# EthernetPhy.net
KiCad netlist of a schematic drawn in Altium Designer
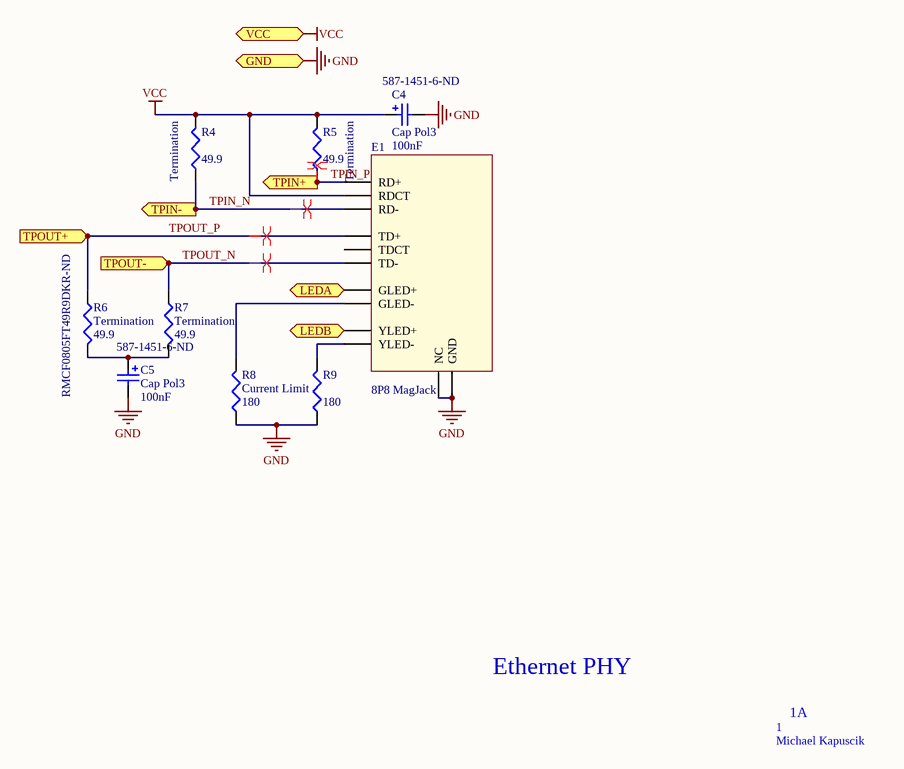
[diagram p0: EthernetPhy.SchDoc]

(export (version "E")
  (design (tool "Eeschema 10.0.6"))
  (components
    (comp (ref "C4")
      (value "Cap Pol3")
      (footprint "C0805")
      (description "Polarized Capacitor (Surface Mount)")
      (fields
        (field (name "ALTIUM_VALUE") "100nF")
        (field (name "SUPPLIER PART NUMBER 1") "587-1451-6-ND")
        (field (name "MANUFACTURER") "Taiyo Yuden")
        (field (name "MANUFACTURER PART NUMBER") "EMK105B7104KV-F")
        (field (name "PUBLISHER") "Altium Limited")
      )
      (libsource (lib "Miscellaneous Devices") (part "Cap Pol3"))
    )
    (comp (ref "C5")
      (value "Cap Pol3")
      (footprint "C0805")
      (description "Polarized Capacitor (Surface Mount)")
      (fields
        (field (name "ALTIUM_VALUE") "100nF")
        (field (name "SUPPLIER PART NUMBER 1") "587-1451-6-ND")
        (field (name "MANUFACTURER") "Taiyo Yuden")
        (field (name "MANUFACTURER PART NUMBER") "EMK105B7104KV-F")
        (field (name "PUBLISHER") "Altium Limited")
      )
      (libsource (lib "Miscellaneous Devices") (part "Cap Pol3"))
    )
    (comp (ref "E1")
      (value "8P8 MagJack")
      (footprint "HR911105")
      (libsource (lib "Miscellaneous Devices") (part "8P8 MagJack"))
    )
    (comp (ref "R4")
      (value "Termination")
      (footprint "J1-0603")
      (description "Resistor")
      (fields (field (name "ALTIUM_VALUE") "49.9") (field (name "PUBLISHER") "Altium Limited"))
      (libsource (lib "Miscellaneous Devices") (part "Res3"))
    )
    (comp (ref "R5")
      (value "Termination")
      (footprint "J1-0603")
      (description "Resistor")
      (fields (field (name "ALTIUM_VALUE") "49.9") (field (name "PUBLISHER") "Altium Limited"))
      (libsource (lib "Miscellaneous Devices") (part "Res3"))
    )
    (comp (ref "R6")
      (value "Termination")
      (footprint "J1-0603")
      (description "Resistor")
      (fields
        (field (name "ALTIUM_VALUE") "49.9")
        (field (name "SUPPLIER PART NUMBER 1") "RMCF0805FT49R9DKR-ND")
        (field (name "PUBLISHER") "Altium Limited")
      )
      (libsource (lib "Miscellaneous Devices") (part "Res3"))
    )
    (comp (ref "R7")
      (value "Termination")
      (footprint "J1-0603")
      (description "Resistor")
      (fields (field (name "ALTIUM_VALUE") "49.9") (field (name "PUBLISHER") "Altium Limited"))
      (libsource (lib "Miscellaneous Devices") (part "Res3"))
    )
    (comp (ref "R8")
      (value "Current Limit")
      (footprint "J1-0603")
      (description "Resistor")
      (fields (field (name "ALTIUM_VALUE") "180") (field (name "PUBLISHER") "Altium Limited"))
      (libsource (lib "Miscellaneous Devices") (part "Res3"))
    )
    (comp (ref "R9")
      (value "180")
      (footprint "J1-0603")
      (description "Resistor")
      (fields (field (name "Comment") "Current Limit") (field (name "PUBLISHER") "Altium Limited"))
      (libsource (lib "Miscellaneous Devices") (part "Res3"))
    )
  )
  (nets
    (net (code "1") (name "/LEDA") (class "Default")
      (node (ref "E1") (pin "9") (pinfunction "GLED+_9") (pintype "passive"))
    )
    (net (code "2") (name "/LEDB") (class "Default")
      (node (ref "E1") (pin "12") (pinfunction "YLED+_12") (pintype "passive"))
    )
    (net (code "3") (name "/TPIN_N") (class "Default")
      (node (ref "E1") (pin "6") (pinfunction "RD-_6") (pintype "passive"))
      (node (ref "R4") (pin "1") (pinfunction "1_1") (pintype "passive"))
    )
    (net (code "4") (name "/TPIN_P") (class "Default")
      (node (ref "E1") (pin "3") (pinfunction "RD+_3") (pintype "passive"))
      (node (ref "R5") (pin "1") (pinfunction "1_1") (pintype "passive"))
    )
    (net (code "5") (name "/TPOUT_N") (class "Default")
      (node (ref "E1") (pin "2") (pinfunction "TD-_2") (pintype "passive"))
      (node (ref "R7") (pin "1") (pinfunction "1_1") (pintype "passive"))
    )
    (net (code "6") (name "/TPOUT_P") (class "Default")
      (node (ref "E1") (pin "1") (pinfunction "TD+_1") (pintype "passive"))
      (node (ref "R6") (pin "1") (pinfunction "1_1") (pintype "passive"))
    )
    (net (code "7") (name "GND") (class "Default")
      (node (ref "C4") (pin "2") (pinfunction "2_2") (pintype "passive"))
      (node (ref "C5") (pin "2") (pinfunction "2_2") (pintype "passive"))
      (node (ref "E1") (pin "7") (pinfunction "NC_7") (pintype "passive"))
      (node (ref "E1") (pin "8") (pinfunction "GND_8") (pintype "passive"))
      (node (ref "R8") (pin "1") (pinfunction "1_1") (pintype "passive"))
      (node (ref "R9") (pin "1") (pinfunction "1_1") (pintype "passive"))
    )
    (net (code "8") (name "Net-(C5-Pad1)") (class "Default")
      (node (ref "C5") (pin "1") (pinfunction "1_1") (pintype "passive"))
      (node (ref "R6") (pin "2") (pinfunction "2_2") (pintype "passive"))
      (node (ref "R7") (pin "2") (pinfunction "2_2") (pintype "passive"))
    )
    (net (code "9") (name "Net-(E1-GLED-)") (class "Default")
      (node (ref "E1") (pin "10") (pinfunction "GLED-_10") (pintype "passive"))
      (node (ref "R8") (pin "2") (pinfunction "2_2") (pintype "passive"))
    )
    (net (code "10") (name "Net-(E1-YLED-)") (class "Default")
      (node (ref "E1") (pin "11") (pinfunction "YLED-_11") (pintype "passive"))
      (node (ref "R9") (pin "2") (pinfunction "2_2") (pintype "passive"))
    )
    (net (code "11") (name "VCC") (class "Default")
      (node (ref "C4") (pin "1") (pinfunction "1_1") (pintype "passive"))
      (node (ref "E1") (pin "5") (pinfunction "RDCT_5") (pintype "passive"))
      (node (ref "R4") (pin "2") (pinfunction "2_2") (pintype "passive"))
      (node (ref "R5") (pin "2") (pinfunction "2_2") (pintype "passive"))
    )
    (net (code "12") (name "unconnected-(E1-TDCT-Pad4)") (class "Default")
      (node (ref "E1") (pin "4") (pinfunction "TDCT_4") (pintype "passive"))
    )
  )
)
